# DB3000.net
KiCad netlist of a schematic drawn in EAGLE
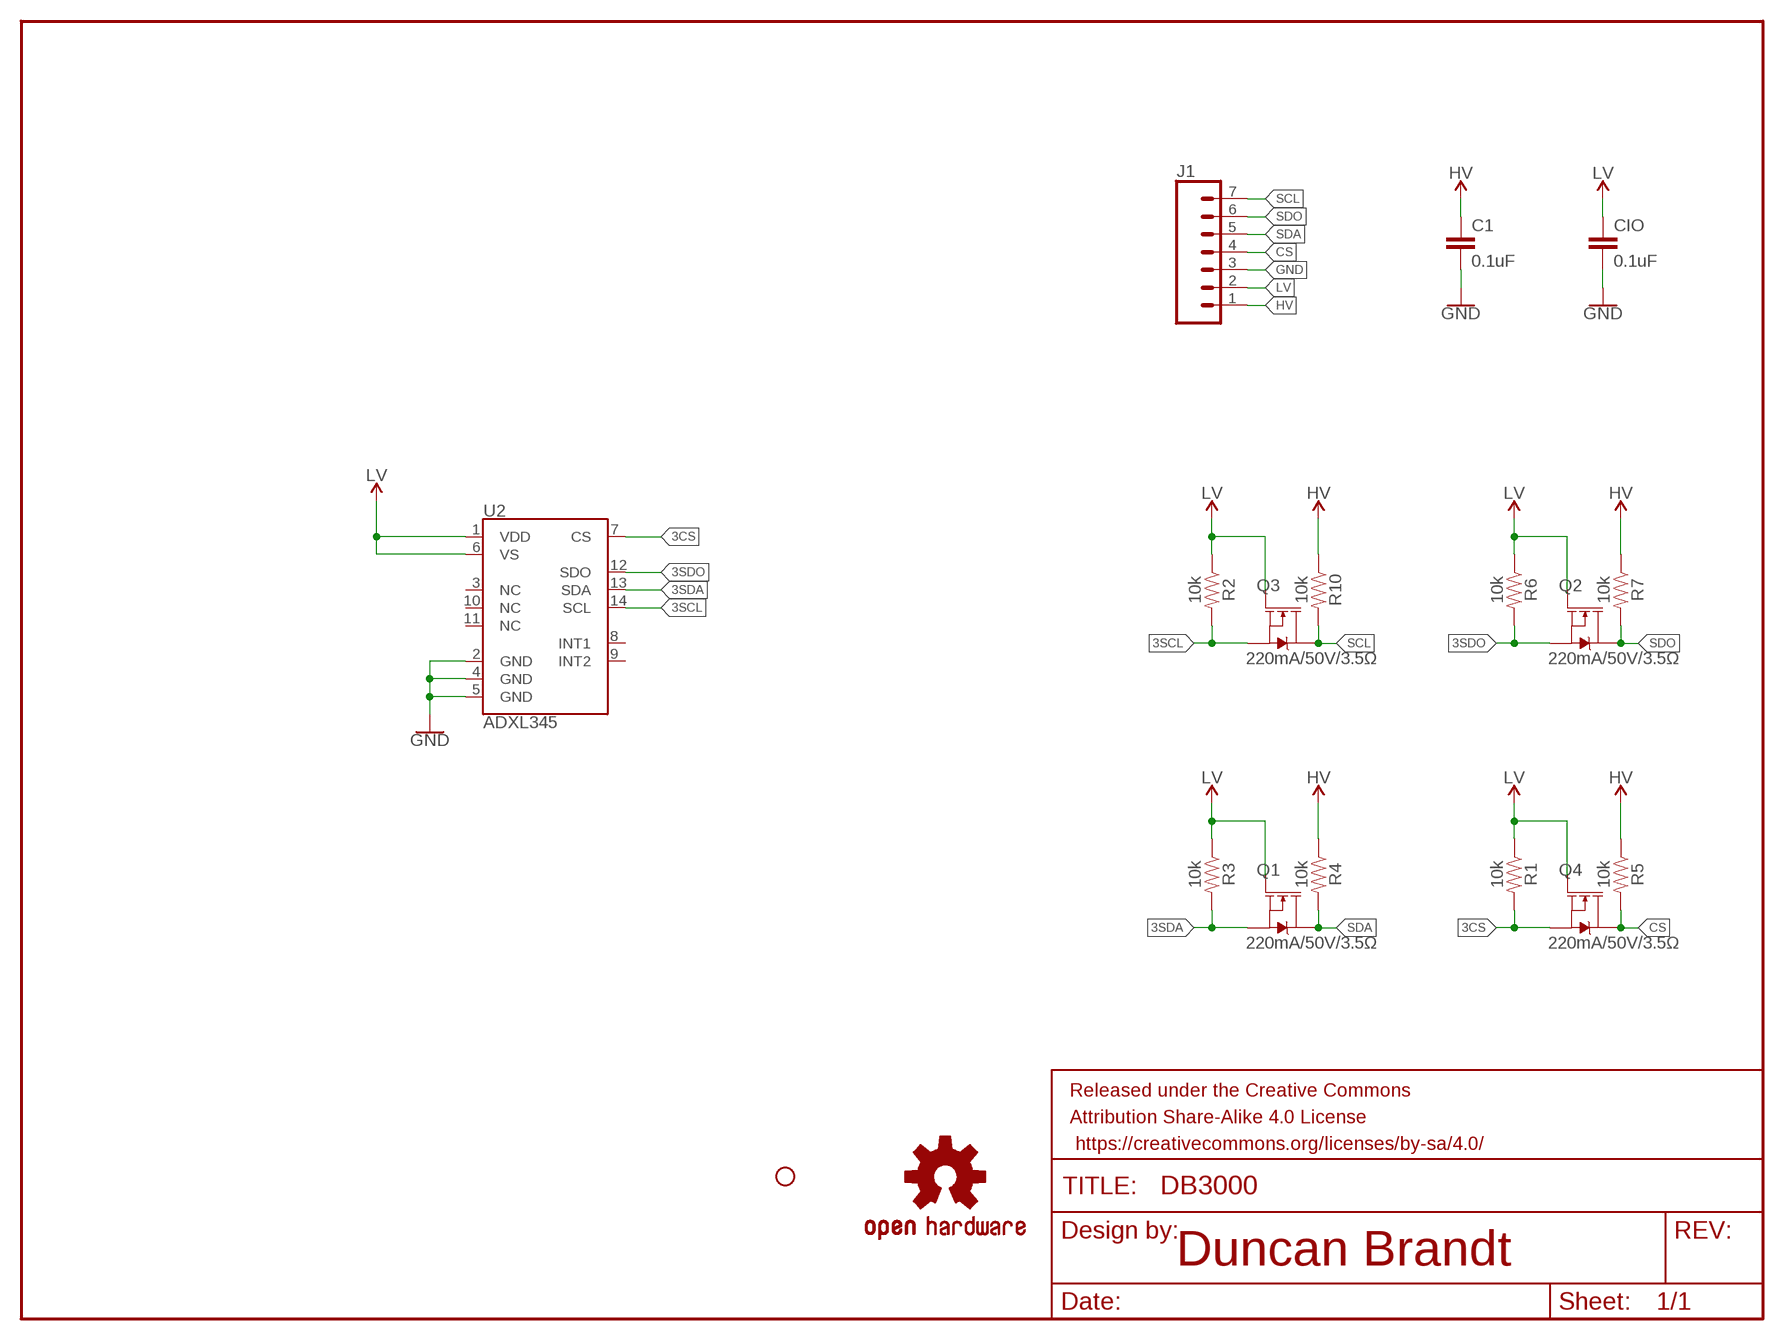
[diagram p0: schematic, sheet 1]

(export (version "E")
  (design (tool "Eeschema 10.0.6"))
  (components
    (comp (ref "C1")
      (value "0.1uF")
      (footprint "eagle-import:0603")
      (libsource (lib "eagle-import") (part "0.1UF-0603-25V-5%"))
    )
    (comp (ref "CIO")
      (value "0.1uF")
      (footprint "eagle-import:0603")
      (libsource (lib "eagle-import") (part "0.1UF-0603-25V-5%"))
    )
    (comp (ref "FRAME1")
      (value "FRAME-LETTER")
      (footprint "eagle-import:CREATIVE_COMMONS")
      (libsource (lib "eagle-import") (part "FRAME-LETTER"))
    )
    (comp (ref "J1")
      (value "CONN_07")
      (footprint "eagle-import:1X07")
      (libsource (lib "eagle-import") (part "CONN_07"))
    )
    (comp (ref "JP3")
      (value "STAND-OFF")
      (footprint "eagle-import:STAND-OFF")
      (libsource (lib "eagle-import") (part "STAND-OFF"))
    )
    (comp (ref "LOGO1")
      (value "OSHW-LOGOL")
      (footprint "eagle-import:OSHW-LOGO-L")
      (libsource (lib "eagle-import") (part "OSHW-LOGOL"))
    )
    (comp (ref "Q1")
      (value "220mA/50V/3.5Ω")
      (footprint "eagle-import:SOT23-3")
      (libsource (lib "eagle-import") (part "MOSFET-NCH-M-BSS138"))
    )
    (comp (ref "Q2")
      (value "220mA/50V/3.5Ω")
      (footprint "eagle-import:SOT23-3")
      (libsource (lib "eagle-import") (part "MOSFET-NCH-M-BSS138"))
    )
    (comp (ref "Q3")
      (value "220mA/50V/3.5Ω")
      (footprint "eagle-import:SOT23-3")
      (libsource (lib "eagle-import") (part "MOSFET-NCH-M-BSS138"))
    )
    (comp (ref "Q4")
      (value "220mA/50V/3.5Ω")
      (footprint "eagle-import:SOT23-3")
      (libsource (lib "eagle-import") (part "MOSFET-NCH-M-BSS138"))
    )
    (comp (ref "R1")
      (value "10k")
      (footprint "eagle-import:0603")
      (libsource (lib "eagle-import") (part "10KOHM-0603-1/10W-1%"))
    )
    (comp (ref "R2")
      (value "10k")
      (footprint "eagle-import:0603")
      (libsource (lib "eagle-import") (part "10KOHM-0603-1/10W-1%"))
    )
    (comp (ref "R3")
      (value "10k")
      (footprint "eagle-import:0603")
      (libsource (lib "eagle-import") (part "10KOHM-0603-1/10W-1%"))
    )
    (comp (ref "R4")
      (value "10k")
      (footprint "eagle-import:0603")
      (libsource (lib "eagle-import") (part "10KOHM-0603-1/10W-1%"))
    )
    (comp (ref "R5")
      (value "10k")
      (footprint "eagle-import:0603")
      (libsource (lib "eagle-import") (part "10KOHM-0603-1/10W-1%"))
    )
    (comp (ref "R6")
      (value "10k")
      (footprint "eagle-import:0603")
      (libsource (lib "eagle-import") (part "10KOHM-0603-1/10W-1%"))
    )
    (comp (ref "R7")
      (value "10k")
      (footprint "eagle-import:0603")
      (libsource (lib "eagle-import") (part "10KOHM-0603-1/10W-1%"))
    )
    (comp (ref "R10")
      (value "10k")
      (footprint "eagle-import:0603")
      (libsource (lib "eagle-import") (part "10KOHM-0603-1/10W-1%"))
    )
    (comp (ref "U2")
      (value "ADXL345")
      (footprint "eagle-import:LGA-14")
      (libsource (lib "eagle-import") (part "ADXL345"))
    )
  )
  (nets
    (net (code "1") (name "3CS") (class "Default")
      (node (ref "Q4") (pin "2") (pinfunction "S_2") (pintype "bidirectional"))
      (node (ref "R1") (pin "2") (pinfunction "2_2") (pintype "passive"))
      (node (ref "U2") (pin "7") (pinfunction "CS_7") (pintype "bidirectional"))
    )
    (net (code "2") (name "3SCL") (class "Default")
      (node (ref "Q3") (pin "2") (pinfunction "S_2") (pintype "bidirectional"))
      (node (ref "R2") (pin "2") (pinfunction "2_2") (pintype "passive"))
      (node (ref "U2") (pin "14") (pinfunction "SCL_14") (pintype "bidirectional"))
    )
    (net (code "3") (name "3SDA") (class "Default")
      (node (ref "Q1") (pin "2") (pinfunction "S_2") (pintype "bidirectional"))
      (node (ref "R3") (pin "2") (pinfunction "2_2") (pintype "passive"))
      (node (ref "U2") (pin "13") (pinfunction "SDA_13") (pintype "bidirectional"))
    )
    (net (code "4") (name "3SDO") (class "Default")
      (node (ref "Q2") (pin "2") (pinfunction "S_2") (pintype "bidirectional"))
      (node (ref "R6") (pin "2") (pinfunction "2_2") (pintype "passive"))
      (node (ref "U2") (pin "12") (pinfunction "SDO_12") (pintype "bidirectional"))
    )
    (net (code "5") (name "CS") (class "Default")
      (node (ref "J1") (pin "4") (pinfunction "4_4") (pintype "passive"))
      (node (ref "Q4") (pin "3") (pinfunction "D_3") (pintype "bidirectional"))
      (node (ref "R5") (pin "2") (pinfunction "2_2") (pintype "passive"))
    )
    (net (code "6") (name "GND") (class "Default")
      (node (ref "C1") (pin "2") (pinfunction "2_2") (pintype "passive"))
      (node (ref "CIO") (pin "2") (pinfunction "2_2") (pintype "passive"))
      (node (ref "J1") (pin "3") (pinfunction "3_3") (pintype "passive"))
      (node (ref "U2") (pin "2") (pinfunction "GND_2") (pintype "bidirectional"))
      (node (ref "U2") (pin "4") (pinfunction "GND_4") (pintype "bidirectional"))
      (node (ref "U2") (pin "5") (pinfunction "GND_5") (pintype "bidirectional"))
    )
    (net (code "7") (name "HV") (class "Default")
      (node (ref "C1") (pin "1") (pinfunction "1_1") (pintype "passive"))
      (node (ref "J1") (pin "1") (pinfunction "1_1") (pintype "passive"))
      (node (ref "R10") (pin "1") (pinfunction "1_1") (pintype "passive"))
      (node (ref "R4") (pin "1") (pinfunction "1_1") (pintype "passive"))
      (node (ref "R5") (pin "1") (pinfunction "1_1") (pintype "passive"))
      (node (ref "R7") (pin "1") (pinfunction "1_1") (pintype "passive"))
    )
    (net (code "8") (name "LV") (class "Default")
      (node (ref "CIO") (pin "1") (pinfunction "1_1") (pintype "passive"))
      (node (ref "J1") (pin "2") (pinfunction "2_2") (pintype "passive"))
      (node (ref "Q1") (pin "1") (pinfunction "G_1") (pintype "bidirectional"))
      (node (ref "Q2") (pin "1") (pinfunction "G_1") (pintype "bidirectional"))
      (node (ref "Q3") (pin "1") (pinfunction "G_1") (pintype "bidirectional"))
      (node (ref "Q4") (pin "1") (pinfunction "G_1") (pintype "bidirectional"))
      (node (ref "R1") (pin "1") (pinfunction "1_1") (pintype "passive"))
      (node (ref "R2") (pin "1") (pinfunction "1_1") (pintype "passive"))
      (node (ref "R3") (pin "1") (pinfunction "1_1") (pintype "passive"))
      (node (ref "R6") (pin "1") (pinfunction "1_1") (pintype "passive"))
      (node (ref "U2") (pin "1") (pinfunction "VDD_1") (pintype "bidirectional"))
      (node (ref "U2") (pin "6") (pinfunction "VS_6") (pintype "bidirectional"))
    )
    (net (code "9") (name "SCL") (class "Default")
      (node (ref "J1") (pin "7") (pinfunction "7_7") (pintype "passive"))
      (node (ref "Q3") (pin "3") (pinfunction "D_3") (pintype "bidirectional"))
      (node (ref "R10") (pin "2") (pinfunction "2_2") (pintype "passive"))
    )
    (net (code "10") (name "SDA") (class "Default")
      (node (ref "J1") (pin "5") (pinfunction "5_5") (pintype "passive"))
      (node (ref "Q1") (pin "3") (pinfunction "D_3") (pintype "bidirectional"))
      (node (ref "R4") (pin "2") (pinfunction "2_2") (pintype "passive"))
    )
    (net (code "11") (name "SDO") (class "Default")
      (node (ref "J1") (pin "6") (pinfunction "6_6") (pintype "passive"))
      (node (ref "Q2") (pin "3") (pinfunction "D_3") (pintype "bidirectional"))
      (node (ref "R7") (pin "2") (pinfunction "2_2") (pintype "passive"))
    )
    (net (code "12") (name "unconnected-(U2-INT1-Pad8)") (class "Default")
      (node (ref "U2") (pin "8") (pinfunction "INT1_8") (pintype "bidirectional"))
    )
    (net (code "13") (name "unconnected-(U2-INT2-Pad9)") (class "Default")
      (node (ref "U2") (pin "9") (pinfunction "INT2_9") (pintype "bidirectional"))
    )
    (net (code "14") (name "unconnected-(U2-NC-Pad3)") (class "Default")
      (node (ref "U2") (pin "3") (pinfunction "NC_3") (pintype "bidirectional"))
    )
    (net (code "15") (name "unconnected-(U2-NC-Pad10)") (class "Default")
      (node (ref "U2") (pin "10") (pinfunction "NC_10") (pintype "bidirectional"))
    )
    (net (code "16") (name "unconnected-(U2-NC-Pad11)") (class "Default")
      (node (ref "U2") (pin "11") (pinfunction "NC_11") (pintype "bidirectional"))
    )
  )
)
